# pdu.net
KiCad netlist of a schematic drawn in EAGLE
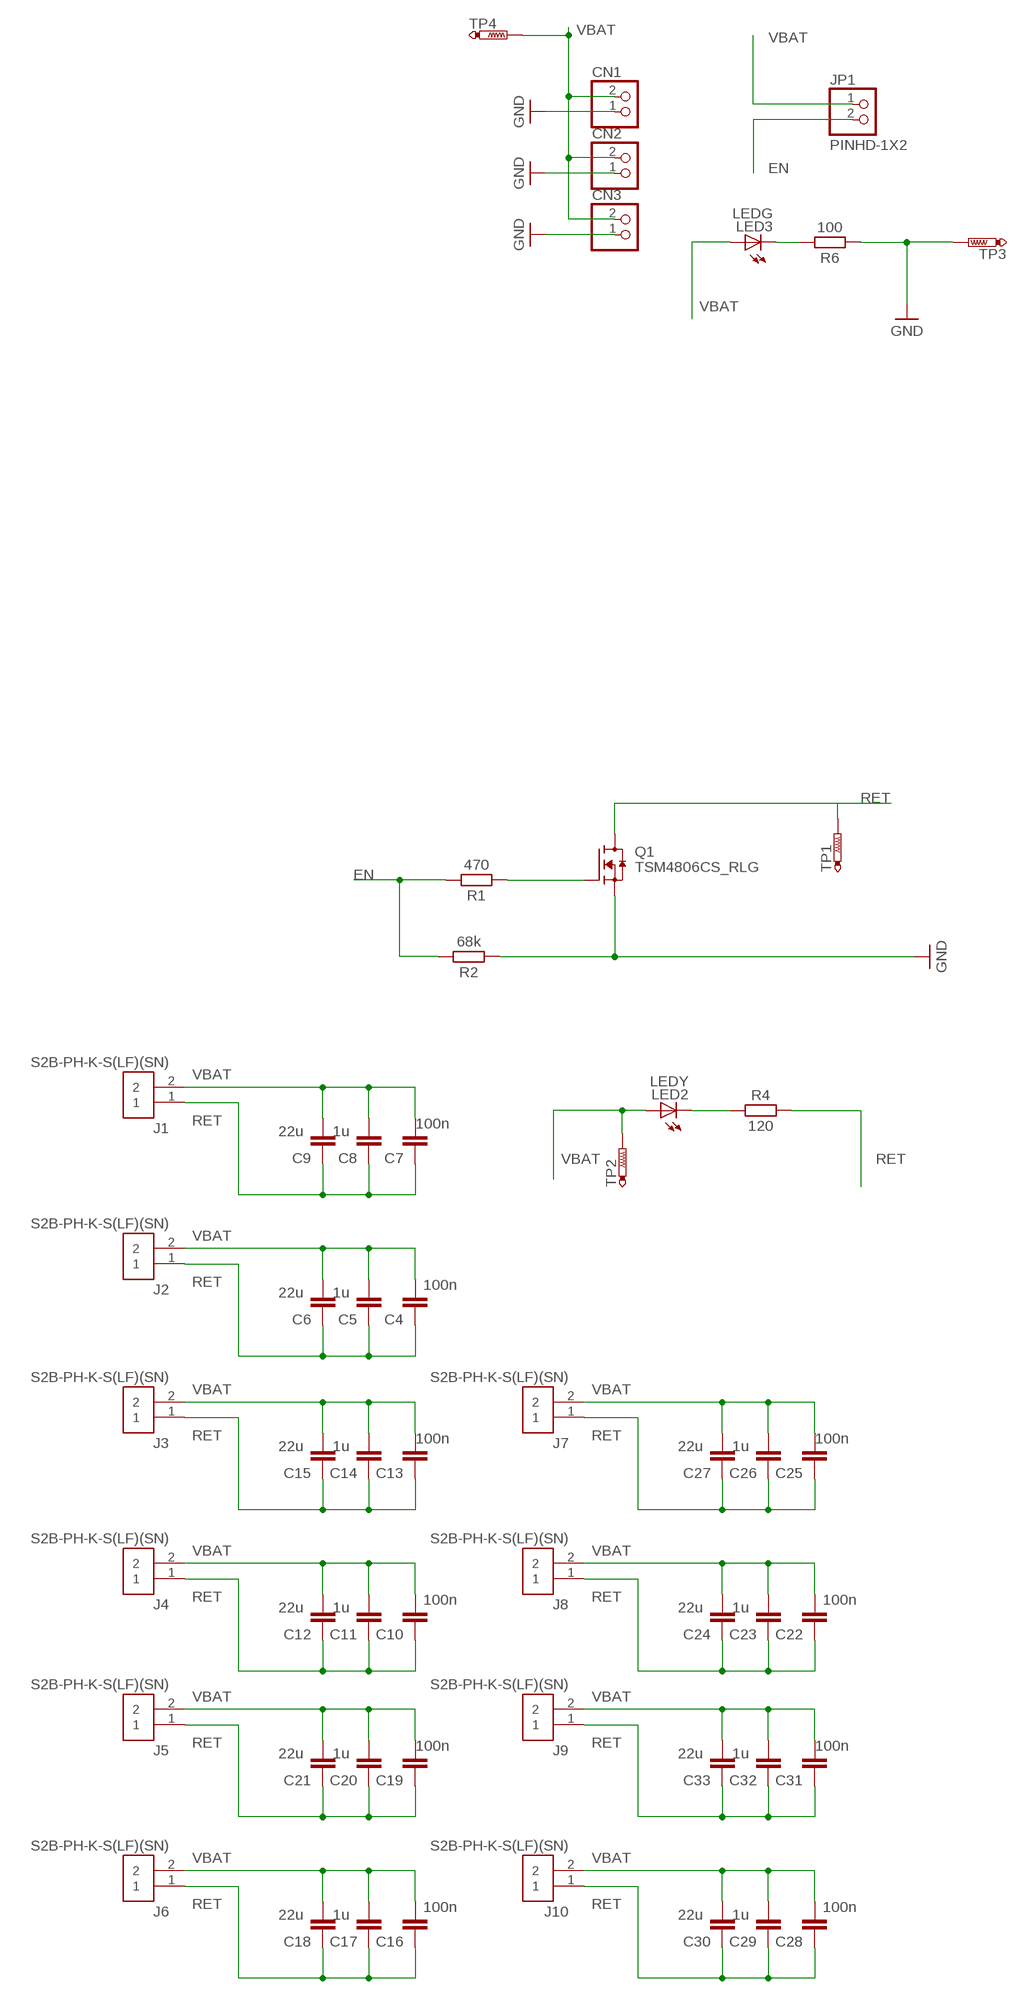
[diagram p0: schematic, sheet 1]

(export (version "E")
  (design (tool "Eeschema 10.0.6"))
  (components
    (comp (ref "C4")
      (value "100n")
      (footprint "eagle-import:CAPC1608X85")
      (libsource (lib "eagle-import") (part "CCHIP-0603(1608-METRIC)_"))
    )
    (comp (ref "C5")
      (value "1u")
      (footprint "eagle-import:CAPC1608X85")
      (libsource (lib "eagle-import") (part "CCHIP-0603(1608-METRIC)_"))
    )
    (comp (ref "C6")
      (value "22u")
      (footprint "eagle-import:CAPC1608X85")
      (libsource (lib "eagle-import") (part "CCHIP-0603(1608-METRIC)_"))
    )
    (comp (ref "C7")
      (value "100n")
      (footprint "eagle-import:CAPC1608X85")
      (libsource (lib "eagle-import") (part "CCHIP-0603(1608-METRIC)_"))
    )
    (comp (ref "C8")
      (value "1u")
      (footprint "eagle-import:CAPC1608X85")
      (libsource (lib "eagle-import") (part "CCHIP-0603(1608-METRIC)_"))
    )
    (comp (ref "C9")
      (value "22u")
      (footprint "eagle-import:CAPC1608X85")
      (libsource (lib "eagle-import") (part "CCHIP-0603(1608-METRIC)_"))
    )
    (comp (ref "C10")
      (value "100n")
      (footprint "eagle-import:CAPC1608X85")
      (libsource (lib "eagle-import") (part "CCHIP-0603(1608-METRIC)_"))
    )
    (comp (ref "C11")
      (value "1u")
      (footprint "eagle-import:CAPC1608X85")
      (libsource (lib "eagle-import") (part "CCHIP-0603(1608-METRIC)_"))
    )
    (comp (ref "C12")
      (value "22u")
      (footprint "eagle-import:CAPC1608X85")
      (libsource (lib "eagle-import") (part "CCHIP-0603(1608-METRIC)_"))
    )
    (comp (ref "C13")
      (value "100n")
      (footprint "eagle-import:CAPC1608X85")
      (libsource (lib "eagle-import") (part "CCHIP-0603(1608-METRIC)_"))
    )
    (comp (ref "C14")
      (value "1u")
      (footprint "eagle-import:CAPC1608X85")
      (libsource (lib "eagle-import") (part "CCHIP-0603(1608-METRIC)_"))
    )
    (comp (ref "C15")
      (value "22u")
      (footprint "eagle-import:CAPC1608X85")
      (libsource (lib "eagle-import") (part "CCHIP-0603(1608-METRIC)_"))
    )
    (comp (ref "C16")
      (value "100n")
      (footprint "eagle-import:CAPC1608X85")
      (libsource (lib "eagle-import") (part "CCHIP-0603(1608-METRIC)_"))
    )
    (comp (ref "C17")
      (value "1u")
      (footprint "eagle-import:CAPC1608X85")
      (libsource (lib "eagle-import") (part "CCHIP-0603(1608-METRIC)_"))
    )
    (comp (ref "C18")
      (value "22u")
      (footprint "eagle-import:CAPC1608X85")
      (libsource (lib "eagle-import") (part "CCHIP-0603(1608-METRIC)_"))
    )
    (comp (ref "C19")
      (value "100n")
      (footprint "eagle-import:CAPC1608X85")
      (libsource (lib "eagle-import") (part "CCHIP-0603(1608-METRIC)_"))
    )
    (comp (ref "C20")
      (value "1u")
      (footprint "eagle-import:CAPC1608X85")
      (libsource (lib "eagle-import") (part "CCHIP-0603(1608-METRIC)_"))
    )
    (comp (ref "C21")
      (value "22u")
      (footprint "eagle-import:CAPC1608X85")
      (libsource (lib "eagle-import") (part "CCHIP-0603(1608-METRIC)_"))
    )
    (comp (ref "C22")
      (value "100n")
      (footprint "eagle-import:CAPC1608X85")
      (libsource (lib "eagle-import") (part "CCHIP-0603(1608-METRIC)_"))
    )
    (comp (ref "C23")
      (value "1u")
      (footprint "eagle-import:CAPC1608X85")
      (libsource (lib "eagle-import") (part "CCHIP-0603(1608-METRIC)_"))
    )
    (comp (ref "C24")
      (value "22u")
      (footprint "eagle-import:CAPC1608X85")
      (libsource (lib "eagle-import") (part "CCHIP-0603(1608-METRIC)_"))
    )
    (comp (ref "C25")
      (value "100n")
      (footprint "eagle-import:CAPC1608X85")
      (libsource (lib "eagle-import") (part "CCHIP-0603(1608-METRIC)_"))
    )
    (comp (ref "C26")
      (value "1u")
      (footprint "eagle-import:CAPC1608X85")
      (libsource (lib "eagle-import") (part "CCHIP-0603(1608-METRIC)_"))
    )
    (comp (ref "C27")
      (value "22u")
      (footprint "eagle-import:CAPC1608X85")
      (libsource (lib "eagle-import") (part "CCHIP-0603(1608-METRIC)_"))
    )
    (comp (ref "C28")
      (value "100n")
      (footprint "eagle-import:CAPC1608X85")
      (libsource (lib "eagle-import") (part "CCHIP-0603(1608-METRIC)_"))
    )
    (comp (ref "C29")
      (value "1u")
      (footprint "eagle-import:CAPC1608X85")
      (libsource (lib "eagle-import") (part "CCHIP-0603(1608-METRIC)_"))
    )
    (comp (ref "C30")
      (value "22u")
      (footprint "eagle-import:CAPC1608X85")
      (libsource (lib "eagle-import") (part "CCHIP-0603(1608-METRIC)_"))
    )
    (comp (ref "C31")
      (value "100n")
      (footprint "eagle-import:CAPC1608X85")
      (libsource (lib "eagle-import") (part "CCHIP-0603(1608-METRIC)_"))
    )
    (comp (ref "C32")
      (value "1u")
      (footprint "eagle-import:CAPC1608X85")
      (libsource (lib "eagle-import") (part "CCHIP-0603(1608-METRIC)_"))
    )
    (comp (ref "C33")
      (value "22u")
      (footprint "eagle-import:CAPC1608X85")
      (libsource (lib "eagle-import") (part "CCHIP-0603(1608-METRIC)_"))
    )
    (comp (ref "CN1")
      (value "JST_2PIN-THM-RA")
      (footprint "eagle-import:JST-PH-2-THM-RA")
      (libsource (lib "eagle-import") (part "JST_2PIN-THM-RA"))
    )
    (comp (ref "CN2")
      (value "JST_2PIN-THM-RA")
      (footprint "eagle-import:JST-PH-2-THM-RA")
      (libsource (lib "eagle-import") (part "JST_2PIN-THM-RA"))
    )
    (comp (ref "CN3")
      (value "JST_2PIN-THM-RA")
      (footprint "eagle-import:JST-PH-2-THM-RA")
      (libsource (lib "eagle-import") (part "JST_2PIN-THM-RA"))
    )
    (comp (ref "J1")
      (value "S2B-PH-K-S(LF)(SN)")
      (footprint "eagle-import:S2B-PH-K-S(LF)(SN)")
      (fields
        (field (name "DIGI_KEY_PART_NUMBER") "455-1719-ND")
        (field (name "MANUFACTURER") "JST Sales America Inc.")
        (field (name "CREATED_BY") "PCBLayout.com")
      )
      (libsource (lib "eagle-import") (part "S2B-PH-K-S(LF)(SN)"))
    )
    (comp (ref "J2")
      (value "S2B-PH-K-S(LF)(SN)")
      (footprint "eagle-import:S2B-PH-K-S(LF)(SN)")
      (fields
        (field (name "DIGI_KEY_PART_NUMBER") "455-1719-ND")
        (field (name "MANUFACTURER") "JST Sales America Inc.")
        (field (name "CREATED_BY") "PCBLayout.com")
      )
      (libsource (lib "eagle-import") (part "S2B-PH-K-S(LF)(SN)"))
    )
    (comp (ref "J3")
      (value "S2B-PH-K-S(LF)(SN)")
      (footprint "eagle-import:S2B-PH-K-S(LF)(SN)")
      (fields
        (field (name "DIGI_KEY_PART_NUMBER") "455-1719-ND")
        (field (name "MANUFACTURER") "JST Sales America Inc.")
        (field (name "CREATED_BY") "PCBLayout.com")
      )
      (libsource (lib "eagle-import") (part "S2B-PH-K-S(LF)(SN)"))
    )
    (comp (ref "J4")
      (value "S2B-PH-K-S(LF)(SN)")
      (footprint "eagle-import:S2B-PH-K-S(LF)(SN)")
      (fields
        (field (name "DIGI_KEY_PART_NUMBER") "455-1719-ND")
        (field (name "MANUFACTURER") "JST Sales America Inc.")
        (field (name "CREATED_BY") "PCBLayout.com")
      )
      (libsource (lib "eagle-import") (part "S2B-PH-K-S(LF)(SN)"))
    )
    (comp (ref "J5")
      (value "S2B-PH-K-S(LF)(SN)")
      (footprint "eagle-import:S2B-PH-K-S(LF)(SN)")
      (fields
        (field (name "DIGI_KEY_PART_NUMBER") "455-1719-ND")
        (field (name "MANUFACTURER") "JST Sales America Inc.")
        (field (name "CREATED_BY") "PCBLayout.com")
      )
      (libsource (lib "eagle-import") (part "S2B-PH-K-S(LF)(SN)"))
    )
    (comp (ref "J6")
      (value "S2B-PH-K-S(LF)(SN)")
      (footprint "eagle-import:S2B-PH-K-S(LF)(SN)")
      (fields
        (field (name "DIGI_KEY_PART_NUMBER") "455-1719-ND")
        (field (name "MANUFACTURER") "JST Sales America Inc.")
        (field (name "CREATED_BY") "PCBLayout.com")
      )
      (libsource (lib "eagle-import") (part "S2B-PH-K-S(LF)(SN)"))
    )
    (comp (ref "J7")
      (value "S2B-PH-K-S(LF)(SN)")
      (footprint "eagle-import:S2B-PH-K-S(LF)(SN)")
      (fields
        (field (name "DIGI_KEY_PART_NUMBER") "455-1719-ND")
        (field (name "MANUFACTURER") "JST Sales America Inc.")
        (field (name "CREATED_BY") "PCBLayout.com")
      )
      (libsource (lib "eagle-import") (part "S2B-PH-K-S(LF)(SN)"))
    )
    (comp (ref "J8")
      (value "S2B-PH-K-S(LF)(SN)")
      (footprint "eagle-import:S2B-PH-K-S(LF)(SN)")
      (fields
        (field (name "DIGI_KEY_PART_NUMBER") "455-1719-ND")
        (field (name "MANUFACTURER") "JST Sales America Inc.")
        (field (name "CREATED_BY") "PCBLayout.com")
      )
      (libsource (lib "eagle-import") (part "S2B-PH-K-S(LF)(SN)"))
    )
    (comp (ref "J9")
      (value "S2B-PH-K-S(LF)(SN)")
      (footprint "eagle-import:S2B-PH-K-S(LF)(SN)")
      (fields
        (field (name "DIGI_KEY_PART_NUMBER") "455-1719-ND")
        (field (name "MANUFACTURER") "JST Sales America Inc.")
        (field (name "CREATED_BY") "PCBLayout.com")
      )
      (libsource (lib "eagle-import") (part "S2B-PH-K-S(LF)(SN)"))
    )
    (comp (ref "J10")
      (value "S2B-PH-K-S(LF)(SN)")
      (footprint "eagle-import:S2B-PH-K-S(LF)(SN)")
      (fields
        (field (name "DIGI_KEY_PART_NUMBER") "455-1719-ND")
        (field (name "MANUFACTURER") "JST Sales America Inc.")
        (field (name "CREATED_BY") "PCBLayout.com")
      )
      (libsource (lib "eagle-import") (part "S2B-PH-K-S(LF)(SN)"))
    )
    (comp (ref "JP1")
      (value "PINHD-1X2")
      (footprint "eagle-import:1X02")
      (fields (field (name "MANUFACTURER") "Generic"))
      (libsource (lib "eagle-import") (part "PINHD-1X2"))
    )
    (comp (ref "LED2")
      (value "LEDY")
      (footprint "eagle-import:CHIPLED_0805")
      (libsource (lib "eagle-import") (part "LEDCHIPLED_0805"))
    )
    (comp (ref "LED3")
      (value "LEDG")
      (footprint "eagle-import:CHIPLED_0805")
      (libsource (lib "eagle-import") (part "LEDCHIPLED_0805"))
    )
    (comp (ref "Q1")
      (value "TSM4806CS_RLG")
      (footprint "eagle-import:SOP127P600X200-8N")
      (fields (field (name "MANUFACTURER") "Taiwan Semiconductor"))
      (libsource (lib "eagle-import") (part "TSM4806CS_RLG"))
    )
    (comp (ref "R1")
      (value "470")
      (footprint "eagle-import:RESC1608X60")
      (libsource (lib "eagle-import") (part "RCHIP-0603(1608-METRIC)_"))
    )
    (comp (ref "R2")
      (value "68k")
      (footprint "eagle-import:RESC1608X60")
      (libsource (lib "eagle-import") (part "RCHIP-0603(1608-METRIC)_"))
    )
    (comp (ref "R4")
      (value "120")
      (footprint "eagle-import:RESC1608X60")
      (libsource (lib "eagle-import") (part "RCHIP-0603(1608-METRIC)_"))
    )
    (comp (ref "R6")
      (value "100")
      (footprint "eagle-import:RESC1608X60")
      (libsource (lib "eagle-import") (part "RCHIP-0603(1608-METRIC)_"))
    )
    (comp (ref "TP1")
      (value "PTR1PAD1-13")
      (footprint "eagle-import:P1-13")
      (libsource (lib "eagle-import") (part "PTR1PAD1-13"))
    )
    (comp (ref "TP2")
      (value "PTR1PAD1-13")
      (footprint "eagle-import:P1-13")
      (libsource (lib "eagle-import") (part "PTR1PAD1-13"))
    )
    (comp (ref "TP3")
      (value "PTR1PAD1-13")
      (footprint "eagle-import:P1-13")
      (libsource (lib "eagle-import") (part "PTR1PAD1-13"))
    )
    (comp (ref "TP4")
      (value "PTR1PAD1-13")
      (footprint "eagle-import:P1-13")
      (libsource (lib "eagle-import") (part "PTR1PAD1-13"))
    )
  )
  (nets
    (net (code "1") (name "/EN") (class "Default")
      (node (ref "JP1") (pin "2") (pinfunction "2_2") (pintype "passive"))
      (node (ref "R1") (pin "2") (pinfunction "2_2") (pintype "passive"))
      (node (ref "R2") (pin "2") (pinfunction "2_2") (pintype "passive"))
    )
    (net (code "2") (name "/RET") (class "Default")
      (node (ref "C10") (pin "1") (pinfunction "1_1") (pintype "passive"))
      (node (ref "C11") (pin "1") (pinfunction "1_1") (pintype "passive"))
      (node (ref "C12") (pin "1") (pinfunction "1_1") (pintype "passive"))
      (node (ref "C13") (pin "1") (pinfunction "1_1") (pintype "passive"))
      (node (ref "C14") (pin "1") (pinfunction "1_1") (pintype "passive"))
      (node (ref "C15") (pin "1") (pinfunction "1_1") (pintype "passive"))
      (node (ref "C16") (pin "1") (pinfunction "1_1") (pintype "passive"))
      (node (ref "C17") (pin "1") (pinfunction "1_1") (pintype "passive"))
      (node (ref "C18") (pin "1") (pinfunction "1_1") (pintype "passive"))
      (node (ref "C19") (pin "1") (pinfunction "1_1") (pintype "passive"))
      (node (ref "C20") (pin "1") (pinfunction "1_1") (pintype "passive"))
      (node (ref "C21") (pin "1") (pinfunction "1_1") (pintype "passive"))
      (node (ref "C22") (pin "1") (pinfunction "1_1") (pintype "passive"))
      (node (ref "C23") (pin "1") (pinfunction "1_1") (pintype "passive"))
      (node (ref "C24") (pin "1") (pinfunction "1_1") (pintype "passive"))
      (node (ref "C25") (pin "1") (pinfunction "1_1") (pintype "passive"))
      (node (ref "C26") (pin "1") (pinfunction "1_1") (pintype "passive"))
      (node (ref "C27") (pin "1") (pinfunction "1_1") (pintype "passive"))
      (node (ref "C28") (pin "1") (pinfunction "1_1") (pintype "passive"))
      (node (ref "C29") (pin "1") (pinfunction "1_1") (pintype "passive"))
      (node (ref "C30") (pin "1") (pinfunction "1_1") (pintype "passive"))
      (node (ref "C31") (pin "1") (pinfunction "1_1") (pintype "passive"))
      (node (ref "C32") (pin "1") (pinfunction "1_1") (pintype "passive"))
      (node (ref "C33") (pin "1") (pinfunction "1_1") (pintype "passive"))
      (node (ref "C4") (pin "1") (pinfunction "1_1") (pintype "passive"))
      (node (ref "C5") (pin "1") (pinfunction "1_1") (pintype "passive"))
      (node (ref "C6") (pin "1") (pinfunction "1_1") (pintype "passive"))
      (node (ref "C7") (pin "1") (pinfunction "1_1") (pintype "passive"))
      (node (ref "C8") (pin "1") (pinfunction "1_1") (pintype "passive"))
      (node (ref "C9") (pin "1") (pinfunction "1_1") (pintype "passive"))
      (node (ref "J1") (pin "1") (pinfunction "1_1") (pintype "passive"))
      (node (ref "J10") (pin "1") (pinfunction "1_1") (pintype "passive"))
      (node (ref "J2") (pin "1") (pinfunction "1_1") (pintype "passive"))
      (node (ref "J3") (pin "1") (pinfunction "1_1") (pintype "passive"))
      (node (ref "J4") (pin "1") (pinfunction "1_1") (pintype "passive"))
      (node (ref "J5") (pin "1") (pinfunction "1_1") (pintype "passive"))
      (node (ref "J6") (pin "1") (pinfunction "1_1") (pintype "passive"))
      (node (ref "J7") (pin "1") (pinfunction "1_1") (pintype "passive"))
      (node (ref "J8") (pin "1") (pinfunction "1_1") (pintype "passive"))
      (node (ref "J9") (pin "1") (pinfunction "1_1") (pintype "passive"))
      (node (ref "Q1") (pin "5") (pinfunction "D_5") (pintype "passive"))
      (node (ref "Q1") (pin "6") (pinfunction "D_6") (pintype "passive"))
      (node (ref "Q1") (pin "7") (pinfunction "D_7") (pintype "passive"))
      (node (ref "Q1") (pin "8") (pinfunction "D_8") (pintype "passive"))
      (node (ref "R4") (pin "2") (pinfunction "2_2") (pintype "passive"))
      (node (ref "TP1") (pin "TP") (pinfunction "TP_TP") (pintype "input"))
    )
    (net (code "3") (name "/VBAT") (class "Default")
      (node (ref "C10") (pin "2") (pinfunction "2_2") (pintype "passive"))
      (node (ref "C11") (pin "2") (pinfunction "2_2") (pintype "passive"))
      (node (ref "C12") (pin "2") (pinfunction "2_2") (pintype "passive"))
      (node (ref "C13") (pin "2") (pinfunction "2_2") (pintype "passive"))
      (node (ref "C14") (pin "2") (pinfunction "2_2") (pintype "passive"))
      (node (ref "C15") (pin "2") (pinfunction "2_2") (pintype "passive"))
      (node (ref "C16") (pin "2") (pinfunction "2_2") (pintype "passive"))
      (node (ref "C17") (pin "2") (pinfunction "2_2") (pintype "passive"))
      (node (ref "C18") (pin "2") (pinfunction "2_2") (pintype "passive"))
      (node (ref "C19") (pin "2") (pinfunction "2_2") (pintype "passive"))
      (node (ref "C20") (pin "2") (pinfunction "2_2") (pintype "passive"))
      (node (ref "C21") (pin "2") (pinfunction "2_2") (pintype "passive"))
      (node (ref "C22") (pin "2") (pinfunction "2_2") (pintype "passive"))
      (node (ref "C23") (pin "2") (pinfunction "2_2") (pintype "passive"))
      (node (ref "C24") (pin "2") (pinfunction "2_2") (pintype "passive"))
      (node (ref "C25") (pin "2") (pinfunction "2_2") (pintype "passive"))
      (node (ref "C26") (pin "2") (pinfunction "2_2") (pintype "passive"))
      (node (ref "C27") (pin "2") (pinfunction "2_2") (pintype "passive"))
      (node (ref "C28") (pin "2") (pinfunction "2_2") (pintype "passive"))
      (node (ref "C29") (pin "2") (pinfunction "2_2") (pintype "passive"))
      (node (ref "C30") (pin "2") (pinfunction "2_2") (pintype "passive"))
      (node (ref "C31") (pin "2") (pinfunction "2_2") (pintype "passive"))
      (node (ref "C32") (pin "2") (pinfunction "2_2") (pintype "passive"))
      (node (ref "C33") (pin "2") (pinfunction "2_2") (pintype "passive"))
      (node (ref "C4") (pin "2") (pinfunction "2_2") (pintype "passive"))
      (node (ref "C5") (pin "2") (pinfunction "2_2") (pintype "passive"))
      (node (ref "C6") (pin "2") (pinfunction "2_2") (pintype "passive"))
      (node (ref "C7") (pin "2") (pinfunction "2_2") (pintype "passive"))
      (node (ref "C8") (pin "2") (pinfunction "2_2") (pintype "passive"))
      (node (ref "C9") (pin "2") (pinfunction "2_2") (pintype "passive"))
      (node (ref "CN1") (pin "2") (pinfunction "1_2") (pintype "passive"))
      (node (ref "CN2") (pin "2") (pinfunction "1_2") (pintype "passive"))
      (node (ref "CN3") (pin "2") (pinfunction "1_2") (pintype "passive"))
      (node (ref "J1") (pin "2") (pinfunction "2_2") (pintype "passive"))
      (node (ref "J10") (pin "2") (pinfunction "2_2") (pintype "passive"))
      (node (ref "J2") (pin "2") (pinfunction "2_2") (pintype "passive"))
      (node (ref "J3") (pin "2") (pinfunction "2_2") (pintype "passive"))
      (node (ref "J4") (pin "2") (pinfunction "2_2") (pintype "passive"))
      (node (ref "J5") (pin "2") (pinfunction "2_2") (pintype "passive"))
      (node (ref "J6") (pin "2") (pinfunction "2_2") (pintype "passive"))
      (node (ref "J7") (pin "2") (pinfunction "2_2") (pintype "passive"))
      (node (ref "J8") (pin "2") (pinfunction "2_2") (pintype "passive"))
      (node (ref "J9") (pin "2") (pinfunction "2_2") (pintype "passive"))
      (node (ref "JP1") (pin "1") (pinfunction "1_1") (pintype "passive"))
      (node (ref "LED2") (pin "A") (pinfunction "A_A") (pintype "passive"))
      (node (ref "LED3") (pin "A") (pinfunction "A_A") (pintype "passive"))
      (node (ref "TP2") (pin "TP") (pinfunction "TP_TP") (pintype "input"))
      (node (ref "TP4") (pin "TP") (pinfunction "TP_TP") (pintype "input"))
    )
    (net (code "4") (name "GND") (class "Default")
      (node (ref "CN1") (pin "1") (pinfunction "2_1") (pintype "passive"))
      (node (ref "CN2") (pin "1") (pinfunction "2_1") (pintype "passive"))
      (node (ref "CN3") (pin "1") (pinfunction "2_1") (pintype "passive"))
      (node (ref "Q1") (pin "1") (pinfunction "S_1") (pintype "passive"))
      (node (ref "Q1") (pin "2") (pinfunction "S_2") (pintype "passive"))
      (node (ref "Q1") (pin "3") (pinfunction "S_3") (pintype "passive"))
      (node (ref "R2") (pin "1") (pinfunction "1_1") (pintype "passive"))
      (node (ref "R6") (pin "1") (pinfunction "1_1") (pintype "passive"))
      (node (ref "TP3") (pin "TP") (pinfunction "TP_TP") (pintype "input"))
    )
    (net (code "5") (name "Net-(LED2-PadC)") (class "Default")
      (node (ref "LED2") (pin "C") (pinfunction "C_C") (pintype "passive"))
      (node (ref "R4") (pin "1") (pinfunction "1_1") (pintype "passive"))
    )
    (net (code "6") (name "Net-(LED3-PadC)") (class "Default")
      (node (ref "LED3") (pin "C") (pinfunction "C_C") (pintype "passive"))
      (node (ref "R6") (pin "2") (pinfunction "2_2") (pintype "passive"))
    )
    (net (code "7") (name "Net-(Q1-G)") (class "Default")
      (node (ref "Q1") (pin "4") (pinfunction "G_4") (pintype "passive"))
      (node (ref "R1") (pin "1") (pinfunction "1_1") (pintype "passive"))
    )
  )
)
